# RADIO.net
KiCad netlist of a schematic drawn in Altium Designer
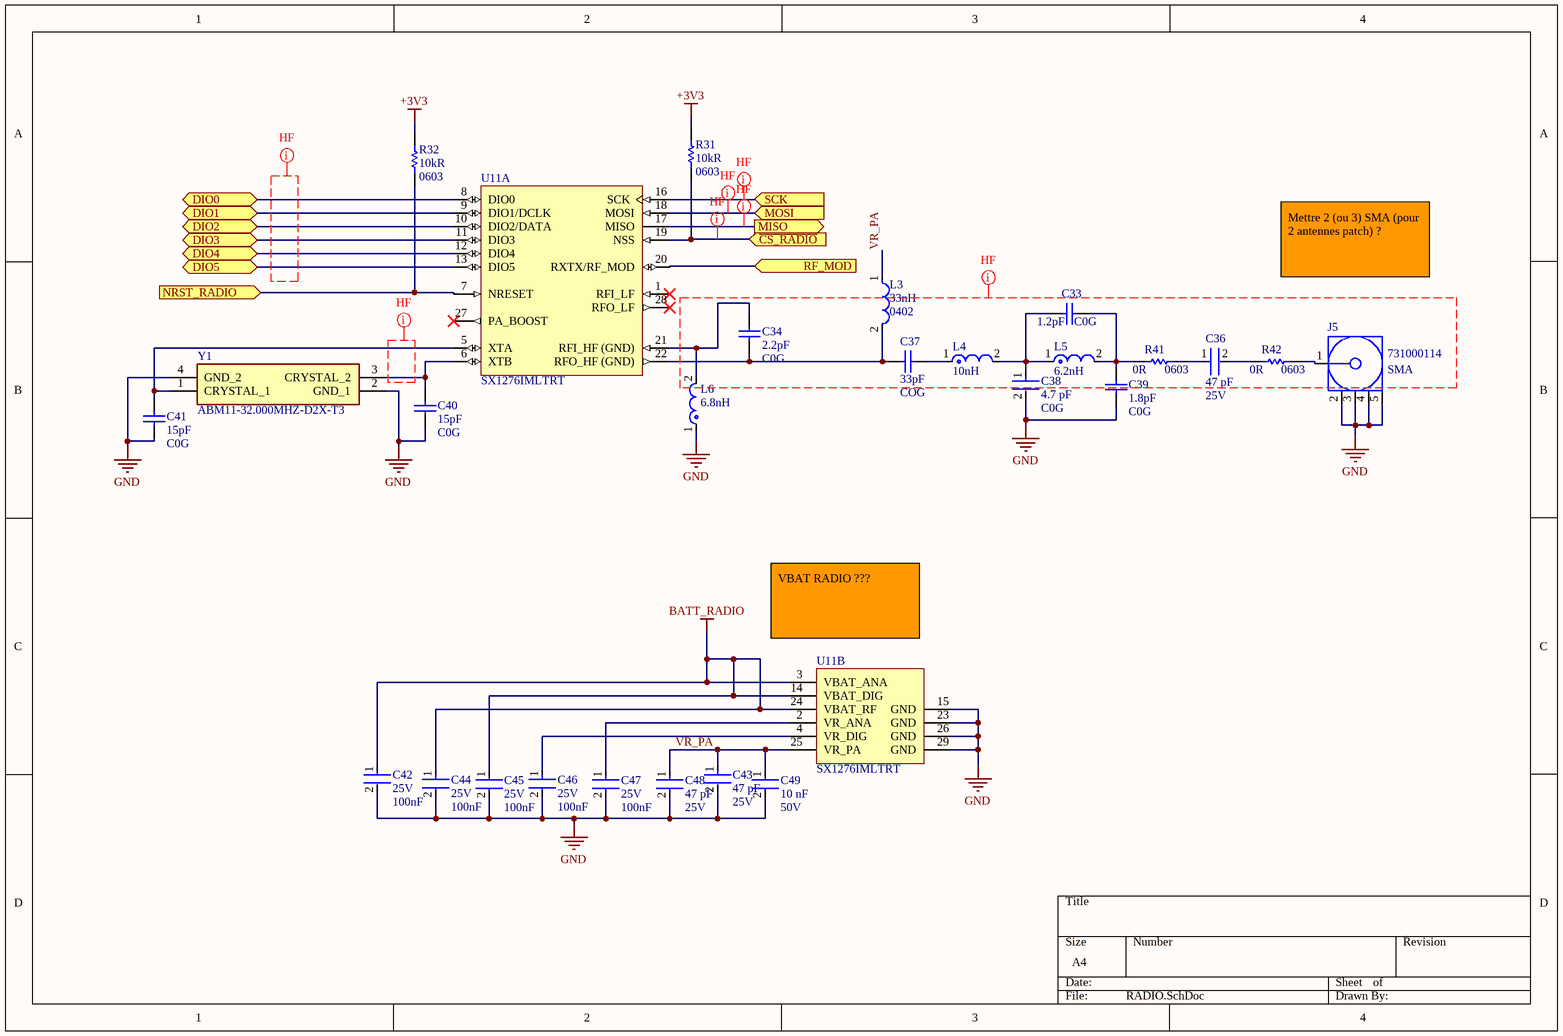
[diagram p0: RADIO.SchDoc]

(export (version "E")
  (design (tool "Eeschema 10.0.6"))
  (components
    (comp (ref "C33")
      (value "06032U1R2BAT2A")
      (footprint "CAPC1508X91X25LL25T13")
      (fields
        (field (name "MANUFACTURER") "AVX Interconnect / Elco")
        (field (name "CAPACITANCE") "1.2pF")
        (field (name "DIELECTRIC") "C0G")
        (field (name "VOLTAGE") "200V")
        (field (name "TOLERANCE") "2%")
      )
      (libsource (lib "Altium Content Vault") (part "CAP"))
    )
    (comp (ref "C34")
      (value "04023A2R2CAT2A")
      (footprint "CAPC1005X56X25ML10T15")
      (fields
        (field (name "MANUFACTURER") "AVX Interconnect / Elco")
        (field (name "CAPACITANCE") "2.2pF")
        (field (name "DIELECTRIC") "C0G")
      )
      (libsource (lib "Altium Content Vault") (part "CAP"))
    )
    (comp (ref "C36")
      (value "C0603C470J3GACTU")
      (footprint "FP-C0603C-CF-MFG")
      (description "CAP CER 47PF 25V 5% NP0 0603")
      (fields
        (field (name "CAPACITANCE") "47 pF")
        (field (name "OCTOPART") "https://octopart.com/c0603c470j3gactu-kemet-8375742")
        (field (name "MANUFACTURER") "KEMET")
        (field (name "VOLTAGE RATING (DC)") "25V")
      )
      (libsource (lib "Altium Content Vault") (part "b4654b650e69147ec39a6b967a45e02"))
    )
    (comp (ref "C37")
      (value "CC0603JRNPO9BN330")
      (footprint "CAPC1608X90X40LL10T20")
      (description "Chip Capacitor, 33 pF, +/- 5%, 50 V, -55 to 125 degC, 0603 (1608 Metric), RoHS, Tape and Reel")
      (fields
        (field (name "MANUFACTURER") "Yageo")
        (field (name "TOLERANCE") "±5%")
        (field (name "CAPACITANCE") "33pF")
        (field (name "TEMPERATURE COEFFICIENT") "COG")
      )
      (libsource (lib "Altium Content Vault") (part "CAP-NP-2"))
    )
    (comp (ref "C38")
      (value "C0603C479C5GACTU")
      (footprint "FP-C0603C-CF-MFG")
      (description "CAP CER 4.7PF 50V NP0 0603")
      (fields
        (field (name "OCTOPART") "https://octopart.com/c0603c479c5gactu-kemet-3648287")
        (field (name "TOLERANCE") "0.25 pF")
        (field (name "CAPACITANCE") "4.7 pF")
        (field (name "TEMPERATURE CHARACTERISTIC") "C0G")
      )
      (libsource (lib "Altium Content Vault") (part "b4654b650e69147ec39a6b967a45e02"))
    )
    (comp (ref "C39")
      (value "06032U1R8BAT2A")
      (footprint "CAPC1508X91X25NL25T13")
      (fields
        (field (name "MANUFACTURER") "AVX Interconnect / Elco")
        (field (name "CAPACITANCE") "1.8pF")
        (field (name "DIELECTRIC") "C0G")
        (field (name "VOLTAGE") "200V")
      )
      (libsource (lib "Altium Content Vault") (part "CAP"))
    )
    (comp (ref "C40")
      (value "VJ0603D150JXPAJ")
      (footprint "CAPC1608X92X38ML15T08")
      (fields
        (field (name "MANUFACTURER") "Vitramon")
        (field (name "TOLERANCE") "5%")
        (field (name "CAPACITANCE") "15pF")
        (field (name "DIELECTRIC") "C0G")
        (field (name "VOLTAGE") "250V")
      )
      (libsource (lib "Altium Content Vault") (part "CAP"))
    )
    (comp (ref "C41")
      (value "VJ0603D150JXPAJ")
      (footprint "CAPC1608X92X38ML15T08")
      (fields
        (field (name "MANUFACTURER") "Vitramon")
        (field (name "TOLERANCE") "5%")
        (field (name "CAPACITANCE") "15pF")
        (field (name "DIELECTRIC") "C0G")
        (field (name "VOLTAGE") "250V")
      )
      (libsource (lib "Altium Content Vault") (part "CAP"))
    )
    (comp (ref "C42")
      (value "CGA3E2X7R1E104K080AA")
      (footprint "FP-CGA3E-0_3-0_1-MFG")
      (description "Cap Ceramic 100nF 25V X7R 10% Pad SMD 0603 +125°C Automotive T/R")
      (fields
        (field (name "VOLTAGE RATING (DC)") "25V")
        (field (name "CAPACITANCE") "100nF")
        (field (name "TOLERANCE") "10%")
        (field (name "MANUFACTURER") "TDK")
      )
      (libsource (lib "Altium Content Vault") (part "b4654b650e69147ec39a6b967a45e02"))
    )
    (comp (ref "C43")
      (value "C0603C470J3GACTU")
      (footprint "FP-C0603C-CF-MFG")
      (description "CAP CER 47PF 25V 5% NP0 0603")
      (fields
        (field (name "CAPACITANCE") "47 pF")
        (field (name "OCTOPART") "https://octopart.com/c0603c470j3gactu-kemet-8375742")
        (field (name "MANUFACTURER") "KEMET")
        (field (name "VOLTAGE RATING (DC)") "25V")
      )
      (libsource (lib "Altium Content Vault") (part "b4654b650e69147ec39a6b967a45e02"))
    )
    (comp (ref "C44")
      (value "CGA3E2X7R1E104K080AA")
      (footprint "FP-CGA3E-0_3-0_1-MFG")
      (description "Cap Ceramic 100nF 25V X7R 10% Pad SMD 0603 +125°C Automotive T/R")
      (fields
        (field (name "VOLTAGE RATING (DC)") "25V")
        (field (name "CAPACITANCE") "100nF")
        (field (name "TOLERANCE") "10%")
        (field (name "MANUFACTURER") "TDK")
      )
      (libsource (lib "Altium Content Vault") (part "b4654b650e69147ec39a6b967a45e02"))
    )
    (comp (ref "C45")
      (value "CGA3E2X7R1E104K080AA")
      (footprint "FP-CGA3E-0_3-0_1-MFG")
      (description "Cap Ceramic 100nF 25V X7R 10% Pad SMD 0603 +125°C Automotive T/R")
      (fields
        (field (name "VOLTAGE RATING (DC)") "25V")
        (field (name "CAPACITANCE") "100nF")
        (field (name "TOLERANCE") "10%")
        (field (name "MANUFACTURER") "TDK")
      )
      (libsource (lib "Altium Content Vault") (part "b4654b650e69147ec39a6b967a45e02"))
    )
    (comp (ref "C46")
      (value "CGA3E2X7R1E104K080AA")
      (footprint "FP-CGA3E-0_3-0_1-MFG")
      (description "Cap Ceramic 100nF 25V X7R 10% Pad SMD 0603 +125°C Automotive T/R")
      (fields
        (field (name "VOLTAGE RATING (DC)") "25V")
        (field (name "CAPACITANCE") "100nF")
        (field (name "TOLERANCE") "10%")
        (field (name "MANUFACTURER") "TDK")
      )
      (libsource (lib "Altium Content Vault") (part "b4654b650e69147ec39a6b967a45e02"))
    )
    (comp (ref "C47")
      (value "CGA3E2X7R1E104K080AA")
      (footprint "FP-CGA3E-0_3-0_1-MFG")
      (description "Cap Ceramic 100nF 25V X7R 10% Pad SMD 0603 +125°C Automotive T/R")
      (fields
        (field (name "VOLTAGE RATING (DC)") "25V")
        (field (name "CAPACITANCE") "100nF")
        (field (name "TOLERANCE") "10%")
        (field (name "MANUFACTURER") "TDK")
      )
      (libsource (lib "Altium Content Vault") (part "b4654b650e69147ec39a6b967a45e02"))
    )
    (comp (ref "C48")
      (value "C0603C470J3GACTU")
      (footprint "FP-C0603C-CF-MFG")
      (description "CAP CER 47PF 25V 5% NP0 0603")
      (fields
        (field (name "CAPACITANCE") "47 pF")
        (field (name "OCTOPART") "https://octopart.com/c0603c470j3gactu-kemet-8375742")
        (field (name "MANUFACTURER") "KEMET")
        (field (name "VOLTAGE RATING (DC)") "25V")
      )
      (libsource (lib "Altium Content Vault") (part "b4654b650e69147ec39a6b967a45e02"))
    )
    (comp (ref "C49")
      (value "CC0603KRX7R9BB103")
      (footprint "FP-CC0603-DA-MFG")
      (description "CAP CER 10000PF 50V X7R 0603")
      (fields
        (field (name "TOLERANCE") "0.1")
        (field (name "MANUFACTURER") "YAGEO")
        (field (name "CAPACITANCE") "10 nF")
        (field (name "VOLTAGE RATING (DC)") "50V")
      )
      (libsource (lib "Altium Content Vault") (part "11868f565c42a9108669ba33697ecf6"))
    )
    (comp (ref "J5")
      (value "731000114")
      (footprint "MOLX-731000114_V")
      (description "SMA Right-Angle PCB Jack Receptacle, Brass Body, Gold Plated, 50 Ohm, 5-Pin THD, RoHS, Tray")
      (fields
        (field (name "MANUFACTURER") "Molex")
        (field (name "MANUFACTURER PART NUMBER") "73100-0114")
        (field (name "CASE/PACKAGE") "SMA")
      )
      (libsource (lib "Altium Content Vault") (part "CN-S-4F-RF5"))
    )
    (comp (ref "L3")
      (value "LQW15AN33NJ00D")
      (footprint "FP-LQW15AN_00-W0_5-0_1-MFG")
      (description "Wire Wound RF Inductor 33nH ±5% 260mA 0.63Ω 0402 (1005)")
      (fields
        (field (name "TOLERANCE") "5%")
        (field (name "INDUCTANCE") "33nH")
        (field (name "CASE/PACKAGE") "0402")
        (field (name "MANUFACTURER") "Murata")
      )
      (libsource (lib "Altium Content Vault") (part "725321dda6339637d4d059423bc1c3c"))
    )
    (comp (ref "L4")
      (value "LQG15HS10NJ02D")
      (footprint "FP-LQG15HH_02-IPC_A")
      (description "Multilayer type RF Inductor 10nH ±5% 0.26Ω 500mA 0402")
      (fields
        (field (name "INDUCTANCE") "10nH")
        (field (name "TOLERANCE") "5%")
        (field (name "MANUFACTURER") "Murata")
      )
      (libsource (lib "Altium Content Vault") (part "4cc4b267dca4c8e51f7102f422741d8"))
    )
    (comp (ref "L5")
      (value "LQG15HS6N2S02D")
      (footprint "FP-LQG15HH_02-IPC_C")
      (description "Multilayer type RF Inductor 6.2nH ±0.3nH 0.2Ω 600mA 0402")
      (fields (field (name "INDUCTANCE") "6.2nH"))
      (libsource (lib "Altium Content Vault") (part "4cc4b267dca4c8e51f7102f422741d8"))
    )
    (comp (ref "L6")
      (value "LQG15HS6N8J02D")
      (footprint "FP-LQG15HH_02-IPC_A")
      (description "Multilayer type RF Inductor 6.8nH ±5% 0.22Ω 600mA 0402")
      (fields
        (field (name "INDUCTANCE") "6.8nH")
        (field (name "TOLERANCE") "5%")
        (field (name "MANUFACTURER") "Murata")
      )
      (libsource (lib "Altium Content Vault") (part "4cc4b267dca4c8e51f7102f422741d8"))
    )
    (comp (ref "R31")
      (value "ERJ3EKF1002V")
      (footprint "RESC1609X55X30LL15T15")
      (description "Chip Resistor, 10 KOhm, +/- 1%, 0.1 W, -55 to 155 degC, 0603 (1608 Metric), RoHS, Tape and Reel")
      (fields
        (field (name "RESISTANCE") "10kR")
        (field (name "CASE CODE (IMPERIAL)") "0603")
        (field (name "TOLERANCE") "1%")
        (field (name "MANUFACTURER") "Panasonic")
      )
      (libsource (lib "Altium Content Vault") (part "RES-2"))
    )
    (comp (ref "R32")
      (value "ERJ3EKF1002V")
      (footprint "RESC1609X55X30LL15T15")
      (description "Chip Resistor, 10 KOhm, +/- 1%, 0.1 W, -55 to 155 degC, 0603 (1608 Metric), RoHS, Tape and Reel")
      (fields
        (field (name "RESISTANCE") "10kR")
        (field (name "CASE CODE (IMPERIAL)") "0603")
        (field (name "TOLERANCE") "1%")
        (field (name "MANUFACTURER") "Panasonic")
      )
      (libsource (lib "Altium Content Vault") (part "RES-2"))
    )
    (comp (ref "R41")
      (value "RC0603JR-070RL")
      (footprint "RESC1608X55X25ML10T15")
      (description "Chip Resistor, 0 Ohm, +/- 5%, 0.1 W, -55 to 155 degC, 0603 (1608 Metric), RoHS, Tape and Reel")
      (fields
        (field (name "TOLERANCE") "5%")
        (field (name "CASE CODE (IMPERIAL)") "0603")
        (field (name "RESISTANCE") "0R")
        (field (name "MANUFACTURER") "Yageo")
      )
      (libsource (lib "Altium Content Vault") (part "RES-2"))
    )
    (comp (ref "R42")
      (value "RC0603JR-070RL")
      (footprint "RESC1608X55X25ML10T15")
      (description "Chip Resistor, 0 Ohm, +/- 5%, 0.1 W, -55 to 155 degC, 0603 (1608 Metric), RoHS, Tape and Reel")
      (fields
        (field (name "TOLERANCE") "5%")
        (field (name "CASE CODE (IMPERIAL)") "0603")
        (field (name "RESISTANCE") "0R")
        (field (name "MANUFACTURER") "Yageo")
      )
      (libsource (lib "Altium Content Vault") (part "RES-2"))
    )
    (comp (ref "U11")
      (value "SX1276IMLTRT")
      (footprint "SMTC-QFN-28_V")
      (description "Low Power Long Range Transceiver, 137 to 1020 MHz, -40 to 85 degC, 28-Pin QFN, RoHS, Tape and Reel")
      (fields (field (name "MANUFACTURER") "Semtech"))
      (libsource (lib "Altium Content Vault") (part "SMTC-SX127X-QFN-28"))
    )
    (comp (ref "Y1")
      (value "ABM11-32.000MHZ-D2X-T3")
      (footprint "SamacSys:ABM1132000MHZD2XT3")
      (description "Crystal or Oscillator")
      (fields (field (name "MOUSER PART NUMBER") "815-ABM11-32-D2XT3"))
      (libsource (lib "*") (part "ABM11-32.000MHZ-D2X-T3"))
    )
  )
  (nets
    (net (code "1") (name "+3V3") (class "Default")
      (node (ref "R31") (pin "2") (pinfunction "2_2") (pintype "passive"))
      (node (ref "R32") (pin "2") (pinfunction "2_2") (pintype "passive"))
    )
    (net (code "2") (name "/CS_RADIO") (class "Default")
      (node (ref "R31") (pin "1") (pinfunction "1_1") (pintype "passive"))
      (node (ref "U11") (pin "19") (pinfunction "NSS_19") (pintype "input"))
    )
    (net (code "3") (name "/DIO0") (class "Default")
      (node (ref "U11") (pin "8") (pinfunction "DIO0_8") (pintype "bidirectional"))
    )
    (net (code "4") (name "/DIO1") (class "Default")
      (node (ref "U11") (pin "9") (pinfunction "DIO1/DCLK_9") (pintype "bidirectional"))
    )
    (net (code "5") (name "/DIO2") (class "Default")
      (node (ref "U11") (pin "10") (pinfunction "DIO2/DATA_10") (pintype "bidirectional"))
    )
    (net (code "6") (name "/DIO3") (class "Default")
      (node (ref "U11") (pin "11") (pinfunction "DIO3_11") (pintype "bidirectional"))
    )
    (net (code "7") (name "/DIO4") (class "Default")
      (node (ref "U11") (pin "12") (pinfunction "DIO4_12") (pintype "bidirectional"))
    )
    (net (code "8") (name "/DIO5") (class "Default")
      (node (ref "U11") (pin "13") (pinfunction "DIO5_13") (pintype "bidirectional"))
    )
    (net (code "9") (name "/MISO") (class "Default")
      (node (ref "U11") (pin "17") (pinfunction "MISO_17") (pintype "tri_state"))
    )
    (net (code "10") (name "/MOSI") (class "Default")
      (node (ref "U11") (pin "18") (pinfunction "MOSI_18") (pintype "input"))
    )
    (net (code "11") (name "/NRST_RADIO") (class "Default")
      (node (ref "R32") (pin "1") (pinfunction "1_1") (pintype "passive"))
      (node (ref "U11") (pin "7") (pinfunction "NRESET_7") (pintype "input"))
    )
    (net (code "12") (name "/RF_MOD") (class "Default")
      (node (ref "U11") (pin "20") (pinfunction "RXTX/RF_MOD_20") (pintype "bidirectional"))
    )
    (net (code "13") (name "/SCK") (class "Default")
      (node (ref "U11") (pin "16") (pinfunction "SCK_16") (pintype "input"))
    )
    (net (code "14") (name "/VR_PA") (class "Default")
      (node (ref "C43") (pin "1") (pinfunction "1_1") (pintype "passive"))
      (node (ref "C48") (pin "1") (pinfunction "1_1") (pintype "passive"))
      (node (ref "C49") (pin "1") (pinfunction "1_1") (pintype "passive"))
      (node (ref "L3") (pin "1") (pinfunction "1_1") (pintype "passive"))
      (node (ref "U11") (pin "25") (pinfunction "VR_PA_25") (pintype "power_in"))
    )
    (net (code "15") (name "BATT_RADIO") (class "Default")
      (node (ref "C42") (pin "1") (pinfunction "1_1") (pintype "passive"))
      (node (ref "C44") (pin "1") (pinfunction "1_1") (pintype "passive"))
      (node (ref "C45") (pin "1") (pinfunction "1_1") (pintype "passive"))
      (node (ref "U11") (pin "14") (pinfunction "VBAT_DIG_14") (pintype "power_in"))
      (node (ref "U11") (pin "24") (pinfunction "VBAT_RF_24") (pintype "power_in"))
      (node (ref "U11") (pin "3") (pinfunction "VBAT_ANA_3") (pintype "power_in"))
    )
    (net (code "16") (name "GND") (class "Default")
      (node (ref "C38") (pin "2") (pinfunction "2_2") (pintype "passive"))
      (node (ref "C39") (pin "1") (pinfunction "1_1") (pintype "passive"))
      (node (ref "C40") (pin "1") (pinfunction "1_1") (pintype "passive"))
      (node (ref "C41") (pin "1") (pinfunction "1_1") (pintype "passive"))
      (node (ref "C42") (pin "2") (pinfunction "2_2") (pintype "passive"))
      (node (ref "C43") (pin "2") (pinfunction "2_2") (pintype "passive"))
      (node (ref "C44") (pin "2") (pinfunction "2_2") (pintype "passive"))
      (node (ref "C45") (pin "2") (pinfunction "2_2") (pintype "passive"))
      (node (ref "C46") (pin "2") (pinfunction "2_2") (pintype "passive"))
      (node (ref "C47") (pin "2") (pinfunction "2_2") (pintype "passive"))
      (node (ref "C48") (pin "2") (pinfunction "2_2") (pintype "passive"))
      (node (ref "C49") (pin "2") (pinfunction "2_2") (pintype "passive"))
      (node (ref "J5") (pin "2") (pinfunction "2_2") (pintype "passive"))
      (node (ref "J5") (pin "3") (pinfunction "3_3") (pintype "passive"))
      (node (ref "J5") (pin "4") (pinfunction "4_4") (pintype "passive"))
      (node (ref "J5") (pin "5") (pinfunction "5_5") (pintype "passive"))
      (node (ref "L6") (pin "1") (pinfunction "1_1") (pintype "passive"))
      (node (ref "U11") (pin "15") (pinfunction "GND_15") (pintype "power_in"))
      (node (ref "U11") (pin "23") (pinfunction "GND_23") (pintype "power_in"))
      (node (ref "U11") (pin "26") (pinfunction "GND_26") (pintype "power_in"))
      (node (ref "U11") (pin "29") (pinfunction "GND_29") (pintype "power_in"))
      (node (ref "Y1") (pin "2") (pinfunction "GND_1_2") (pintype "passive"))
      (node (ref "Y1") (pin "4") (pinfunction "GND_2_4") (pintype "passive"))
    )
    (net (code "17") (name "Net-(C33-Pad1)") (class "Default")
      (node (ref "C33") (pin "1") (pinfunction "1_1") (pintype "passive"))
      (node (ref "C38") (pin "1") (pinfunction "1_1") (pintype "passive"))
      (node (ref "L4") (pin "2") (pinfunction "2_2") (pintype "passive"))
      (node (ref "L5") (pin "1") (pinfunction "1_1") (pintype "passive"))
    )
    (net (code "18") (name "Net-(C33-Pad2)") (class "Default")
      (node (ref "C33") (pin "2") (pinfunction "2_2") (pintype "passive"))
      (node (ref "C39") (pin "2") (pinfunction "2_2") (pintype "passive"))
      (node (ref "L5") (pin "2") (pinfunction "2_2") (pintype "passive"))
      (node (ref "R41") (pin "1") (pinfunction "1_1") (pintype "passive"))
    )
    (net (code "19") (name "Net-(C36-Pad1)") (class "Default")
      (node (ref "C36") (pin "1") (pinfunction "1_1") (pintype "passive"))
      (node (ref "R41") (pin "2") (pinfunction "2_2") (pintype "passive"))
    )
    (net (code "20") (name "Net-(C36-Pad2)") (class "Default")
      (node (ref "C36") (pin "2") (pinfunction "2_2") (pintype "passive"))
      (node (ref "R42") (pin "1") (pinfunction "1_1") (pintype "passive"))
    )
    (net (code "21") (name "Net-(C37-Pad1)") (class "Default")
      (node (ref "C37") (pin "1") (pinfunction "1_1") (pintype "passive"))
      (node (ref "L4") (pin "1") (pinfunction "1_1") (pintype "passive"))
    )
    (net (code "22") (name "Net-(J5-Pad1)") (class "Default")
      (node (ref "J5") (pin "1") (pinfunction "1_1") (pintype "passive"))
      (node (ref "R42") (pin "2") (pinfunction "2_2") (pintype "passive"))
    )
    (net (code "23") (name "Net-(U11A-RFI_HF_(GND))") (class "Default")
      (node (ref "C34") (pin "1") (pinfunction "1_1") (pintype "passive"))
      (node (ref "L6") (pin "2") (pinfunction "2_2") (pintype "passive"))
      (node (ref "U11") (pin "21") (pinfunction "RFI_HF_(GND)_21") (pintype "input"))
    )
    (net (code "24") (name "Net-(U11A-RFO_HF_(GND))") (class "Default")
      (node (ref "C34") (pin "2") (pinfunction "2_2") (pintype "passive"))
      (node (ref "C37") (pin "2") (pinfunction "2_2") (pintype "passive"))
      (node (ref "L3") (pin "2") (pinfunction "2_2") (pintype "passive"))
      (node (ref "U11") (pin "22") (pinfunction "RFO_HF_(GND)_22") (pintype "output"))
    )
    (net (code "25") (name "Net-(U11A-XTA)") (class "Default")
      (node (ref "C41") (pin "2") (pinfunction "2_2") (pintype "passive"))
      (node (ref "U11") (pin "5") (pinfunction "XTA_5") (pintype "bidirectional"))
      (node (ref "Y1") (pin "1") (pinfunction "CRYSTAL_1_1") (pintype "passive"))
    )
    (net (code "26") (name "Net-(U11A-XTB)") (class "Default")
      (node (ref "C40") (pin "2") (pinfunction "2_2") (pintype "passive"))
      (node (ref "U11") (pin "6") (pinfunction "XTB_6") (pintype "bidirectional"))
      (node (ref "Y1") (pin "3") (pinfunction "CRYSTAL_2_3") (pintype "passive"))
    )
    (net (code "27") (name "Net-(U11B-VR_ANA)") (class "Default")
      (node (ref "C47") (pin "1") (pinfunction "1_1") (pintype "passive"))
      (node (ref "U11") (pin "2") (pinfunction "VR_ANA_2") (pintype "power_in"))
    )
    (net (code "28") (name "Net-(U11B-VR_DIG)") (class "Default")
      (node (ref "C46") (pin "1") (pinfunction "1_1") (pintype "passive"))
      (node (ref "U11") (pin "4") (pinfunction "VR_DIG_4") (pintype "power_in"))
    )
    (net (code "29") (name "unconnected-(U11A-PA_BOOST-Pad27)") (class "Default")
      (node (ref "U11") (pin "27") (pinfunction "PA_BOOST_27") (pintype "output+no_connect"))
    )
    (net (code "30") (name "unconnected-(U11A-RFI_LF-Pad1)") (class "Default")
      (node (ref "U11") (pin "1") (pinfunction "RFI_LF_1") (pintype "input+no_connect"))
    )
    (net (code "31") (name "unconnected-(U11A-RFO_LF-Pad28)") (class "Default")
      (node (ref "U11") (pin "28") (pinfunction "RFO_LF_28") (pintype "output+no_connect"))
    )
  )
)
